# S203X.net
KiCad netlist of a schematic drawn in EAGLE
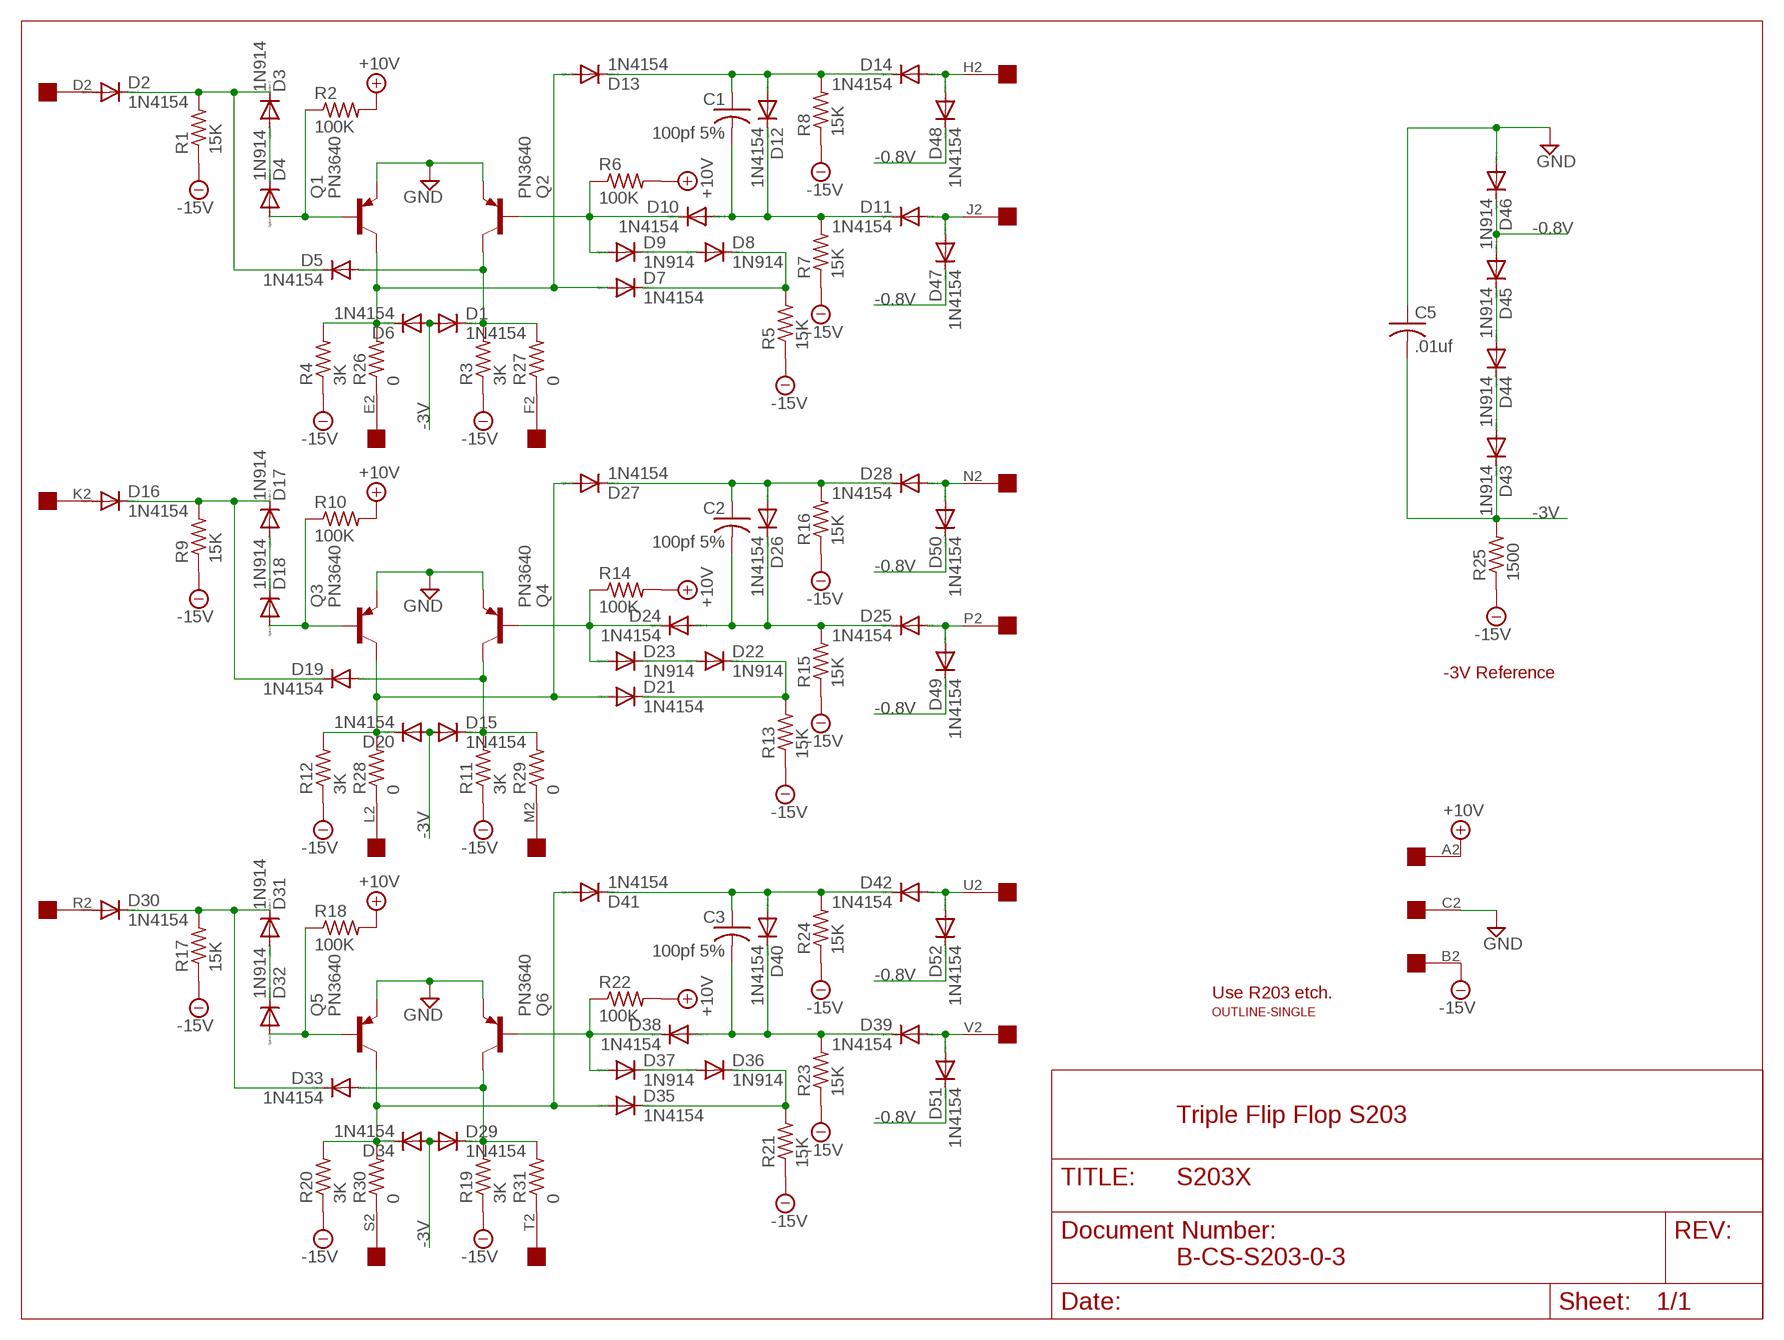
[diagram p0: schematic, sheet 1]

(export (version "E")
  (design (tool "Eeschema 10.0.6"))
  (components
    (comp (ref "C1")
      (value "100pf 5%")
      (footprint "eagle-import:C050-025X075")
      (libsource (lib "eagle-import") (part "C-US050-025X075"))
    )
    (comp (ref "C2")
      (value "100pf 5%")
      (footprint "eagle-import:C050-025X075")
      (libsource (lib "eagle-import") (part "C-US050-025X075"))
    )
    (comp (ref "C3")
      (value "100pf 5%")
      (footprint "eagle-import:C050-025X075")
      (libsource (lib "eagle-import") (part "C-US050-025X075"))
    )
    (comp (ref "C5")
      (value ".01uf")
      (footprint "eagle-import:C050-025X075")
      (libsource (lib "eagle-import") (part "C-US050-025X075"))
    )
    (comp (ref "D1")
      (value "1N4154")
      (footprint "eagle-import:DO35-10")
      (libsource (lib "eagle-import") (part "1N4148DO35-10"))
    )
    (comp (ref "D2")
      (value "1N4154")
      (footprint "eagle-import:DO35-10")
      (libsource (lib "eagle-import") (part "1N4148DO35-10"))
    )
    (comp (ref "D3")
      (value "1N914")
      (footprint "eagle-import:DO35-10")
      (libsource (lib "eagle-import") (part "1N4148DO35-10"))
    )
    (comp (ref "D4")
      (value "1N914")
      (footprint "eagle-import:DO35-10")
      (libsource (lib "eagle-import") (part "1N4148DO35-10"))
    )
    (comp (ref "D5")
      (value "1N4154")
      (footprint "eagle-import:DO35-10")
      (libsource (lib "eagle-import") (part "1N4148DO35-10"))
    )
    (comp (ref "D6")
      (value "1N4154")
      (footprint "eagle-import:DO35-10")
      (libsource (lib "eagle-import") (part "1N4148DO35-10"))
    )
    (comp (ref "D7")
      (value "1N4154")
      (footprint "eagle-import:DO35-10")
      (libsource (lib "eagle-import") (part "1N4148DO35-10"))
    )
    (comp (ref "D8")
      (value "1N914")
      (footprint "eagle-import:DO35-10")
      (libsource (lib "eagle-import") (part "1N4148DO35-10"))
    )
    (comp (ref "D9")
      (value "1N914")
      (footprint "eagle-import:DO35-10")
      (libsource (lib "eagle-import") (part "1N4148DO35-10"))
    )
    (comp (ref "D10")
      (value "1N4154")
      (footprint "eagle-import:DO35-10")
      (libsource (lib "eagle-import") (part "1N4148DO35-10"))
    )
    (comp (ref "D11")
      (value "1N4154")
      (footprint "eagle-import:DO35-10")
      (libsource (lib "eagle-import") (part "1N4148DO35-10"))
    )
    (comp (ref "D12")
      (value "1N4154")
      (footprint "eagle-import:DO35-10")
      (libsource (lib "eagle-import") (part "1N4148DO35-10"))
    )
    (comp (ref "D13")
      (value "1N4154")
      (footprint "eagle-import:DO35-10")
      (libsource (lib "eagle-import") (part "1N4148DO35-10"))
    )
    (comp (ref "D14")
      (value "1N4154")
      (footprint "eagle-import:DO35-10")
      (libsource (lib "eagle-import") (part "1N4148DO35-10"))
    )
    (comp (ref "D15")
      (value "1N4154")
      (footprint "eagle-import:DO35-10")
      (libsource (lib "eagle-import") (part "1N4148DO35-10"))
    )
    (comp (ref "D16")
      (value "1N4154")
      (footprint "eagle-import:DO35-10")
      (libsource (lib "eagle-import") (part "1N4148DO35-10"))
    )
    (comp (ref "D17")
      (value "1N914")
      (footprint "eagle-import:DO35-10")
      (libsource (lib "eagle-import") (part "1N4148DO35-10"))
    )
    (comp (ref "D18")
      (value "1N914")
      (footprint "eagle-import:DO35-10")
      (libsource (lib "eagle-import") (part "1N4148DO35-10"))
    )
    (comp (ref "D19")
      (value "1N4154")
      (footprint "eagle-import:DO35-10")
      (libsource (lib "eagle-import") (part "1N4148DO35-10"))
    )
    (comp (ref "D20")
      (value "1N4154")
      (footprint "eagle-import:DO35-10")
      (libsource (lib "eagle-import") (part "1N4148DO35-10"))
    )
    (comp (ref "D21")
      (value "1N4154")
      (footprint "eagle-import:DO35-10")
      (libsource (lib "eagle-import") (part "1N4148DO35-10"))
    )
    (comp (ref "D22")
      (value "1N914")
      (footprint "eagle-import:DO35-10")
      (libsource (lib "eagle-import") (part "1N4148DO35-10"))
    )
    (comp (ref "D23")
      (value "1N914")
      (footprint "eagle-import:DO35-10")
      (libsource (lib "eagle-import") (part "1N4148DO35-10"))
    )
    (comp (ref "D24")
      (value "1N4154")
      (footprint "eagle-import:DO35-10")
      (libsource (lib "eagle-import") (part "1N4148DO35-10"))
    )
    (comp (ref "D25")
      (value "1N4154")
      (footprint "eagle-import:DO35-10")
      (libsource (lib "eagle-import") (part "1N4148DO35-10"))
    )
    (comp (ref "D26")
      (value "1N4154")
      (footprint "eagle-import:DO35-10")
      (libsource (lib "eagle-import") (part "1N4148DO35-10"))
    )
    (comp (ref "D27")
      (value "1N4154")
      (footprint "eagle-import:DO35-10")
      (libsource (lib "eagle-import") (part "1N4148DO35-10"))
    )
    (comp (ref "D28")
      (value "1N4154")
      (footprint "eagle-import:DO35-10")
      (libsource (lib "eagle-import") (part "1N4148DO35-10"))
    )
    (comp (ref "D29")
      (value "1N4154")
      (footprint "eagle-import:DO35-10")
      (libsource (lib "eagle-import") (part "1N4148DO35-10"))
    )
    (comp (ref "D30")
      (value "1N4154")
      (footprint "eagle-import:DO35-10")
      (libsource (lib "eagle-import") (part "1N4148DO35-10"))
    )
    (comp (ref "D31")
      (value "1N914")
      (footprint "eagle-import:DO35-10")
      (libsource (lib "eagle-import") (part "1N4148DO35-10"))
    )
    (comp (ref "D32")
      (value "1N914")
      (footprint "eagle-import:DO35-10")
      (libsource (lib "eagle-import") (part "1N4148DO35-10"))
    )
    (comp (ref "D33")
      (value "1N4154")
      (footprint "eagle-import:DO35-10")
      (libsource (lib "eagle-import") (part "1N4148DO35-10"))
    )
    (comp (ref "D34")
      (value "1N4154")
      (footprint "eagle-import:DO35-10")
      (libsource (lib "eagle-import") (part "1N4148DO35-10"))
    )
    (comp (ref "D35")
      (value "1N4154")
      (footprint "eagle-import:DO35-10")
      (libsource (lib "eagle-import") (part "1N4148DO35-10"))
    )
    (comp (ref "D36")
      (value "1N914")
      (footprint "eagle-import:DO35-10")
      (libsource (lib "eagle-import") (part "1N4148DO35-10"))
    )
    (comp (ref "D37")
      (value "1N914")
      (footprint "eagle-import:DO35-10")
      (libsource (lib "eagle-import") (part "1N4148DO35-10"))
    )
    (comp (ref "D38")
      (value "1N4154")
      (footprint "eagle-import:DO35-10")
      (libsource (lib "eagle-import") (part "1N4148DO35-10"))
    )
    (comp (ref "D39")
      (value "1N4154")
      (footprint "eagle-import:DO35-10")
      (libsource (lib "eagle-import") (part "1N4148DO35-10"))
    )
    (comp (ref "D40")
      (value "1N4154")
      (footprint "eagle-import:DO35-10")
      (libsource (lib "eagle-import") (part "1N4148DO35-10"))
    )
    (comp (ref "D41")
      (value "1N4154")
      (footprint "eagle-import:DO35-10")
      (libsource (lib "eagle-import") (part "1N4148DO35-10"))
    )
    (comp (ref "D42")
      (value "1N4154")
      (footprint "eagle-import:DO35-10")
      (libsource (lib "eagle-import") (part "1N4148DO35-10"))
    )
    (comp (ref "D43")
      (value "1N914")
      (footprint "eagle-import:DO35-10")
      (libsource (lib "eagle-import") (part "1N4148DO35-10"))
    )
    (comp (ref "D44")
      (value "1N914")
      (footprint "eagle-import:DO35-10")
      (libsource (lib "eagle-import") (part "1N4148DO35-10"))
    )
    (comp (ref "D45")
      (value "1N914")
      (footprint "eagle-import:DO35-10")
      (libsource (lib "eagle-import") (part "1N4148DO35-10"))
    )
    (comp (ref "D46")
      (value "1N914")
      (footprint "eagle-import:DO35-10")
      (libsource (lib "eagle-import") (part "1N4148DO35-10"))
    )
    (comp (ref "D47")
      (value "1N4154")
      (footprint "eagle-import:DO35-10")
      (libsource (lib "eagle-import") (part "1N4148DO35-10"))
    )
    (comp (ref "D48")
      (value "1N4154")
      (footprint "eagle-import:DO35-10")
      (libsource (lib "eagle-import") (part "1N4148DO35-10"))
    )
    (comp (ref "D49")
      (value "1N4154")
      (footprint "eagle-import:DO35-10")
      (libsource (lib "eagle-import") (part "1N4148DO35-10"))
    )
    (comp (ref "D50")
      (value "1N4154")
      (footprint "eagle-import:DO35-10")
      (libsource (lib "eagle-import") (part "1N4148DO35-10"))
    )
    (comp (ref "D51")
      (value "1N4154")
      (footprint "eagle-import:DO35-10")
      (libsource (lib "eagle-import") (part "1N4148DO35-10"))
    )
    (comp (ref "D52")
      (value "1N4154")
      (footprint "eagle-import:DO35-10")
      (libsource (lib "eagle-import") (part "1N4148DO35-10"))
    )
    (comp (ref "Q1")
      (value "PN3640")
      (footprint "eagle-import:TO39")
      (libsource (lib "eagle-import") (part "2N3637"))
    )
    (comp (ref "Q2")
      (value "PN3640")
      (footprint "eagle-import:TO39")
      (libsource (lib "eagle-import") (part "2N3637"))
    )
    (comp (ref "Q3")
      (value "PN3640")
      (footprint "eagle-import:TO39")
      (libsource (lib "eagle-import") (part "2N3637"))
    )
    (comp (ref "Q4")
      (value "PN3640")
      (footprint "eagle-import:TO39")
      (libsource (lib "eagle-import") (part "2N3637"))
    )
    (comp (ref "Q5")
      (value "PN3640")
      (footprint "eagle-import:TO39")
      (libsource (lib "eagle-import") (part "2N3637"))
    )
    (comp (ref "Q6")
      (value "PN3640")
      (footprint "eagle-import:TO39")
      (libsource (lib "eagle-import") (part "2N3637"))
    )
    (comp (ref "R1")
      (value "15K")
      (footprint "eagle-import:0207_10")
      (libsource (lib "eagle-import") (part "R-US_0207/10"))
    )
    (comp (ref "R2")
      (value "100K")
      (footprint "eagle-import:0207_10")
      (libsource (lib "eagle-import") (part "R-US_0207/10"))
    )
    (comp (ref "R3")
      (value "3K")
      (footprint "eagle-import:0207_10")
      (libsource (lib "eagle-import") (part "R-US_0207/10"))
    )
    (comp (ref "R4")
      (value "3K")
      (footprint "eagle-import:0207_10")
      (libsource (lib "eagle-import") (part "R-US_0207/10"))
    )
    (comp (ref "R5")
      (value "15K")
      (footprint "eagle-import:0207_10")
      (libsource (lib "eagle-import") (part "R-US_0207/10"))
    )
    (comp (ref "R6")
      (value "100K")
      (footprint "eagle-import:0207_10")
      (libsource (lib "eagle-import") (part "R-US_0207/10"))
    )
    (comp (ref "R7")
      (value "15K")
      (footprint "eagle-import:0207_10")
      (libsource (lib "eagle-import") (part "R-US_0207/10"))
    )
    (comp (ref "R8")
      (value "15K")
      (footprint "eagle-import:0207_10")
      (libsource (lib "eagle-import") (part "R-US_0207/10"))
    )
    (comp (ref "R9")
      (value "15K")
      (footprint "eagle-import:0207_10")
      (libsource (lib "eagle-import") (part "R-US_0207/10"))
    )
    (comp (ref "R10")
      (value "100K")
      (footprint "eagle-import:0207_10")
      (libsource (lib "eagle-import") (part "R-US_0207/10"))
    )
    (comp (ref "R11")
      (value "3K")
      (footprint "eagle-import:0207_10")
      (libsource (lib "eagle-import") (part "R-US_0207/10"))
    )
    (comp (ref "R12")
      (value "3K")
      (footprint "eagle-import:0207_10")
      (libsource (lib "eagle-import") (part "R-US_0207/10"))
    )
    (comp (ref "R13")
      (value "15K")
      (footprint "eagle-import:0207_10")
      (libsource (lib "eagle-import") (part "R-US_0207/10"))
    )
    (comp (ref "R14")
      (value "100K")
      (footprint "eagle-import:0207_10")
      (libsource (lib "eagle-import") (part "R-US_0207/10"))
    )
    (comp (ref "R15")
      (value "15K")
      (footprint "eagle-import:0207_10")
      (libsource (lib "eagle-import") (part "R-US_0207/10"))
    )
    (comp (ref "R16")
      (value "15K")
      (footprint "eagle-import:0207_10")
      (libsource (lib "eagle-import") (part "R-US_0207/10"))
    )
    (comp (ref "R17")
      (value "15K")
      (footprint "eagle-import:0207_10")
      (libsource (lib "eagle-import") (part "R-US_0207/10"))
    )
    (comp (ref "R18")
      (value "100K")
      (footprint "eagle-import:0207_10")
      (libsource (lib "eagle-import") (part "R-US_0207/10"))
    )
    (comp (ref "R19")
      (value "3K")
      (footprint "eagle-import:0207_10")
      (libsource (lib "eagle-import") (part "R-US_0207/10"))
    )
    (comp (ref "R20")
      (value "3K")
      (footprint "eagle-import:0207_10")
      (libsource (lib "eagle-import") (part "R-US_0207/10"))
    )
    (comp (ref "R21")
      (value "15K")
      (footprint "eagle-import:0207_10")
      (libsource (lib "eagle-import") (part "R-US_0207/10"))
    )
    (comp (ref "R22")
      (value "100K")
      (footprint "eagle-import:0207_10")
      (libsource (lib "eagle-import") (part "R-US_0207/10"))
    )
    (comp (ref "R23")
      (value "15K")
      (footprint "eagle-import:0207_10")
      (libsource (lib "eagle-import") (part "R-US_0207/10"))
    )
    (comp (ref "R24")
      (value "15K")
      (footprint "eagle-import:0207_10")
      (libsource (lib "eagle-import") (part "R-US_0207/10"))
    )
    (comp (ref "R25")
      (value "1500")
      (footprint "eagle-import:0207_10")
      (libsource (lib "eagle-import") (part "R-US_0207/10"))
    )
    (comp (ref "R26")
      (value "0")
      (footprint "eagle-import:0207_10")
      (libsource (lib "eagle-import") (part "R-US_0207/10"))
    )
    (comp (ref "R27")
      (value "0")
      (footprint "eagle-import:0207_10")
      (libsource (lib "eagle-import") (part "R-US_0207/10"))
    )
    (comp (ref "R28")
      (value "0")
      (footprint "eagle-import:0207_10")
      (libsource (lib "eagle-import") (part "R-US_0207/10"))
    )
    (comp (ref "R29")
      (value "0")
      (footprint "eagle-import:0207_10")
      (libsource (lib "eagle-import") (part "R-US_0207/10"))
    )
    (comp (ref "R30")
      (value "0")
      (footprint "eagle-import:0207_10")
      (libsource (lib "eagle-import") (part "R-US_0207/10"))
    )
    (comp (ref "R31")
      (value "0")
      (footprint "eagle-import:0207_10")
      (libsource (lib "eagle-import") (part "R-US_0207/10"))
    )
    (comp (ref "U$1")
      (value "OUTLINE-SINGLE")
      (footprint "eagle-import:SINGLE")
      (libsource (lib "eagle-import") (part "OUTLINE-SINGLE"))
    )
    (comp (ref "U$2")
      (value "EDGE-1")
      (footprint "eagle-import:EDGE-CON1")
      (libsource (lib "eagle-import") (part "EDGE-1"))
    )
  )
  (nets
    (net (code "1") (name "+10V") (class "Default")
      (node (ref "R10") (pin "2") (pinfunction "2_2") (pintype "passive"))
      (node (ref "R14") (pin "2") (pinfunction "2_2") (pintype "passive"))
      (node (ref "R18") (pin "2") (pinfunction "2_2") (pintype "passive"))
      (node (ref "R2") (pin "2") (pinfunction "2_2") (pintype "passive"))
      (node (ref "R22") (pin "2") (pinfunction "2_2") (pintype "passive"))
      (node (ref "R6") (pin "2") (pinfunction "2_2") (pintype "passive"))
      (node (ref "U$2") (pin "A2") (pinfunction "1_A2") (pintype "bidirectional"))
    )
    (net (code "2") (name "-15V") (class "Default")
      (node (ref "R1") (pin "1") (pinfunction "1_1") (pintype "passive"))
      (node (ref "R11") (pin "1") (pinfunction "1_1") (pintype "passive"))
      (node (ref "R12") (pin "1") (pinfunction "1_1") (pintype "passive"))
      (node (ref "R13") (pin "1") (pinfunction "1_1") (pintype "passive"))
      (node (ref "R15") (pin "1") (pinfunction "1_1") (pintype "passive"))
      (node (ref "R16") (pin "1") (pinfunction "1_1") (pintype "passive"))
      (node (ref "R17") (pin "1") (pinfunction "1_1") (pintype "passive"))
      (node (ref "R19") (pin "1") (pinfunction "1_1") (pintype "passive"))
      (node (ref "R20") (pin "1") (pinfunction "1_1") (pintype "passive"))
      (node (ref "R21") (pin "1") (pinfunction "1_1") (pintype "passive"))
      (node (ref "R23") (pin "1") (pinfunction "1_1") (pintype "passive"))
      (node (ref "R24") (pin "1") (pinfunction "1_1") (pintype "passive"))
      (node (ref "R25") (pin "1") (pinfunction "1_1") (pintype "passive"))
      (node (ref "R3") (pin "1") (pinfunction "1_1") (pintype "passive"))
      (node (ref "R4") (pin "1") (pinfunction "1_1") (pintype "passive"))
      (node (ref "R5") (pin "1") (pinfunction "1_1") (pintype "passive"))
      (node (ref "R7") (pin "1") (pinfunction "1_1") (pintype "passive"))
      (node (ref "R8") (pin "1") (pinfunction "1_1") (pintype "passive"))
      (node (ref "R9") (pin "1") (pinfunction "1_1") (pintype "passive"))
      (node (ref "U$2") (pin "B2") (pinfunction "1_B2") (pintype "bidirectional"))
    )
    (net (code "3") (name "/-0.8V") (class "Default")
      (node (ref "D45") (pin "A") (pinfunction "A_A") (pintype "passive"))
      (node (ref "D46") (pin "C") (pinfunction "C_C") (pintype "passive"))
      (node (ref "D47") (pin "C") (pinfunction "C_C") (pintype "passive"))
      (node (ref "D48") (pin "C") (pinfunction "C_C") (pintype "passive"))
      (node (ref "D49") (pin "C") (pinfunction "C_C") (pintype "passive"))
      (node (ref "D50") (pin "C") (pinfunction "C_C") (pintype "passive"))
      (node (ref "D51") (pin "C") (pinfunction "C_C") (pintype "passive"))
      (node (ref "D52") (pin "C") (pinfunction "C_C") (pintype "passive"))
    )
    (net (code "4") (name "/-3V") (class "Default")
      (node (ref "C5") (pin "2") (pinfunction "2_2") (pintype "passive"))
      (node (ref "D1") (pin "A") (pinfunction "A_A") (pintype "passive"))
      (node (ref "D15") (pin "A") (pinfunction "A_A") (pintype "passive"))
      (node (ref "D20") (pin "A") (pinfunction "A_A") (pintype "passive"))
      (node (ref "D29") (pin "A") (pinfunction "A_A") (pintype "passive"))
      (node (ref "D34") (pin "A") (pinfunction "A_A") (pintype "passive"))
      (node (ref "D43") (pin "C") (pinfunction "C_C") (pintype "passive"))
      (node (ref "D6") (pin "A") (pinfunction "A_A") (pintype "passive"))
      (node (ref "R25") (pin "2") (pinfunction "2_2") (pintype "passive"))
    )
    (net (code "5") (name "GND") (class "Default")
      (node (ref "C5") (pin "1") (pinfunction "1_1") (pintype "passive"))
      (node (ref "D46") (pin "A") (pinfunction "A_A") (pintype "passive"))
      (node (ref "Q1") (pin "1") (pinfunction "E_1") (pintype "passive"))
      (node (ref "Q2") (pin "1") (pinfunction "E_1") (pintype "passive"))
      (node (ref "Q3") (pin "1") (pinfunction "E_1") (pintype "passive"))
      (node (ref "Q4") (pin "1") (pinfunction "E_1") (pintype "passive"))
      (node (ref "Q5") (pin "1") (pinfunction "E_1") (pintype "passive"))
      (node (ref "Q6") (pin "1") (pinfunction "E_1") (pintype "passive"))
      (node (ref "U$2") (pin "C2") (pinfunction "1_C2") (pintype "bidirectional"))
    )
    (net (code "6") (name "Net-(C1-Pad1)") (class "Default")
      (node (ref "C1") (pin "1") (pinfunction "1_1") (pintype "passive"))
      (node (ref "D12") (pin "A") (pinfunction "A_A") (pintype "passive"))
      (node (ref "D13") (pin "C") (pinfunction "C_C") (pintype "passive"))
      (node (ref "D14") (pin "C") (pinfunction "C_C") (pintype "passive"))
      (node (ref "R8") (pin "2") (pinfunction "2_2") (pintype "passive"))
    )
    (net (code "7") (name "Net-(C1-Pad2)") (class "Default")
      (node (ref "C1") (pin "2") (pinfunction "2_2") (pintype "passive"))
      (node (ref "D10") (pin "A") (pinfunction "A_A") (pintype "passive"))
      (node (ref "D11") (pin "C") (pinfunction "C_C") (pintype "passive"))
      (node (ref "D12") (pin "C") (pinfunction "C_C") (pintype "passive"))
      (node (ref "R7") (pin "2") (pinfunction "2_2") (pintype "passive"))
    )
    (net (code "8") (name "Net-(C2-Pad1)") (class "Default")
      (node (ref "C2") (pin "1") (pinfunction "1_1") (pintype "passive"))
      (node (ref "D26") (pin "A") (pinfunction "A_A") (pintype "passive"))
      (node (ref "D27") (pin "C") (pinfunction "C_C") (pintype "passive"))
      (node (ref "D28") (pin "C") (pinfunction "C_C") (pintype "passive"))
      (node (ref "R16") (pin "2") (pinfunction "2_2") (pintype "passive"))
    )
    (net (code "9") (name "Net-(C2-Pad2)") (class "Default")
      (node (ref "C2") (pin "2") (pinfunction "2_2") (pintype "passive"))
      (node (ref "D24") (pin "A") (pinfunction "A_A") (pintype "passive"))
      (node (ref "D25") (pin "C") (pinfunction "C_C") (pintype "passive"))
      (node (ref "D26") (pin "C") (pinfunction "C_C") (pintype "passive"))
      (node (ref "R15") (pin "2") (pinfunction "2_2") (pintype "passive"))
    )
    (net (code "10") (name "Net-(C3-Pad1)") (class "Default")
      (node (ref "C3") (pin "1") (pinfunction "1_1") (pintype "passive"))
      (node (ref "D40") (pin "A") (pinfunction "A_A") (pintype "passive"))
      (node (ref "D41") (pin "C") (pinfunction "C_C") (pintype "passive"))
      (node (ref "D42") (pin "C") (pinfunction "C_C") (pintype "passive"))
      (node (ref "R24") (pin "2") (pinfunction "2_2") (pintype "passive"))
    )
    (net (code "11") (name "Net-(C3-Pad2)") (class "Default")
      (node (ref "C3") (pin "2") (pinfunction "2_2") (pintype "passive"))
      (node (ref "D38") (pin "A") (pinfunction "A_A") (pintype "passive"))
      (node (ref "D39") (pin "C") (pinfunction "C_C") (pintype "passive"))
      (node (ref "D40") (pin "C") (pinfunction "C_C") (pintype "passive"))
      (node (ref "R23") (pin "2") (pinfunction "2_2") (pintype "passive"))
    )
    (net (code "12") (name "Net-(D2-PadC)") (class "Default")
      (node (ref "D2") (pin "C") (pinfunction "C_C") (pintype "passive"))
      (node (ref "D3") (pin "C") (pinfunction "C_C") (pintype "passive"))
      (node (ref "D5") (pin "C") (pinfunction "C_C") (pintype "passive"))
      (node (ref "R1") (pin "2") (pinfunction "2_2") (pintype "passive"))
    )
    (net (code "13") (name "Net-(D3-PadA)") (class "Default")
      (node (ref "D3") (pin "A") (pinfunction "A_A") (pintype "passive"))
      (node (ref "D4") (pin "C") (pinfunction "C_C") (pintype "passive"))
    )
    (net (code "14") (name "Net-(D7-PadC)") (class "Default")
      (node (ref "D7") (pin "C") (pinfunction "C_C") (pintype "passive"))
      (node (ref "D8") (pin "C") (pinfunction "C_C") (pintype "passive"))
      (node (ref "R5") (pin "2") (pinfunction "2_2") (pintype "passive"))
    )
    (net (code "15") (name "Net-(D8-PadA)") (class "Default")
      (node (ref "D8") (pin "A") (pinfunction "A_A") (pintype "passive"))
      (node (ref "D9") (pin "C") (pinfunction "C_C") (pintype "passive"))
    )
    (net (code "16") (name "Net-(D16-PadC)") (class "Default")
      (node (ref "D16") (pin "C") (pinfunction "C_C") (pintype "passive"))
      (node (ref "D17") (pin "C") (pinfunction "C_C") (pintype "passive"))
      (node (ref "D19") (pin "C") (pinfunction "C_C") (pintype "passive"))
      (node (ref "R9") (pin "2") (pinfunction "2_2") (pintype "passive"))
    )
    (net (code "17") (name "Net-(D17-PadA)") (class "Default")
      (node (ref "D17") (pin "A") (pinfunction "A_A") (pintype "passive"))
      (node (ref "D18") (pin "C") (pinfunction "C_C") (pintype "passive"))
    )
    (net (code "18") (name "Net-(D21-PadC)") (class "Default")
      (node (ref "D21") (pin "C") (pinfunction "C_C") (pintype "passive"))
      (node (ref "D22") (pin "C") (pinfunction "C_C") (pintype "passive"))
      (node (ref "R13") (pin "2") (pinfunction "2_2") (pintype "passive"))
    )
    (net (code "19") (name "Net-(D22-PadA)") (class "Default")
      (node (ref "D22") (pin "A") (pinfunction "A_A") (pintype "passive"))
      (node (ref "D23") (pin "C") (pinfunction "C_C") (pintype "passive"))
    )
    (net (code "20") (name "Net-(D30-PadC)") (class "Default")
      (node (ref "D30") (pin "C") (pinfunction "C_C") (pintype "passive"))
      (node (ref "D31") (pin "C") (pinfunction "C_C") (pintype "passive"))
      (node (ref "D33") (pin "C") (pinfunction "C_C") (pintype "passive"))
      (node (ref "R17") (pin "2") (pinfunction "2_2") (pintype "passive"))
    )
    (net (code "21") (name "Net-(D31-PadA)") (class "Default")
      (node (ref "D31") (pin "A") (pinfunction "A_A") (pintype "passive"))
      (node (ref "D32") (pin "C") (pinfunction "C_C") (pintype "passive"))
    )
    (net (code "22") (name "Net-(D35-PadC)") (class "Default")
      (node (ref "D35") (pin "C") (pinfunction "C_C") (pintype "passive"))
      (node (ref "D36") (pin "C") (pinfunction "C_C") (pintype "passive"))
      (node (ref "R21") (pin "2") (pinfunction "2_2") (pintype "passive"))
    )
    (net (code "23") (name "Net-(D36-PadA)") (class "Default")
      (node (ref "D36") (pin "A") (pinfunction "A_A") (pintype "passive"))
      (node (ref "D37") (pin "C") (pinfunction "C_C") (pintype "passive"))
    )
    (net (code "24") (name "Net-(D43-PadA)") (class "Default")
      (node (ref "D43") (pin "A") (pinfunction "A_A") (pintype "passive"))
      (node (ref "D44") (pin "C") (pinfunction "C_C") (pintype "passive"))
    )
    (net (code "25") (name "Net-(D44-PadA)") (class "Default")
      (node (ref "D44") (pin "A") (pinfunction "A_A") (pintype "passive"))
      (node (ref "D45") (pin "C") (pinfunction "C_C") (pintype "passive"))
    )
    (net (code "26") (name "Net-(Q1-B)") (class "Default")
      (node (ref "D4") (pin "A") (pinfunction "A_A") (pintype "passive"))
      (node (ref "Q1") (pin "2") (pinfunction "B_2") (pintype "passive"))
      (node (ref "R2") (pin "1") (pinfunction "1_1") (pintype "passive"))
    )
    (net (code "27") (name "Net-(Q1-C)") (class "Default")
      (node (ref "D13") (pin "A") (pinfunction "A_A") (pintype "passive"))
      (node (ref "D6") (pin "C") (pinfunction "C_C") (pintype "passive"))
      (node (ref "D7") (pin "A") (pinfunction "A_A") (pintype "passive"))
      (node (ref "Q1") (pin "3") (pinfunction "C_3") (pintype "passive"))
      (node (ref "R26") (pin "2") (pinfunction "2_2") (pintype "passive"))
      (node (ref "R4") (pin "2") (pinfunction "2_2") (pintype "passive"))
    )
    (net (code "28") (name "Net-(Q2-B)") (class "Default")
      (node (ref "D10") (pin "C") (pinfunction "C_C") (pintype "passive"))
      (node (ref "D9") (pin "A") (pinfunction "A_A") (pintype "passive"))
      (node (ref "Q2") (pin "2") (pinfunction "B_2") (pintype "passive"))
      (node (ref "R6") (pin "1") (pinfunction "1_1") (pintype "passive"))
    )
    (net (code "29") (name "Net-(Q2-C)") (class "Default")
      (node (ref "D1") (pin "C") (pinfunction "C_C") (pintype "passive"))
      (node (ref "D5") (pin "A") (pinfunction "A_A") (pintype "passive"))
      (node (ref "Q2") (pin "3") (pinfunction "C_3") (pintype "passive"))
      (node (ref "R27") (pin "2") (pinfunction "2_2") (pintype "passive"))
      (node (ref "R3") (pin "2") (pinfunction "2_2") (pintype "passive"))
    )
    (net (code "30") (name "Net-(Q3-B)") (class "Default")
      (node (ref "D18") (pin "A") (pinfunction "A_A") (pintype "passive"))
      (node (ref "Q3") (pin "2") (pinfunction "B_2") (pintype "passive"))
      (node (ref "R10") (pin "1") (pinfunction "1_1") (pintype "passive"))
    )
    (net (code "31") (name "Net-(Q3-C)") (class "Default")
      (node (ref "D20") (pin "C") (pinfunction "C_C") (pintype "passive"))
      (node (ref "D21") (pin "A") (pinfunction "A_A") (pintype "passive"))
      (node (ref "D27") (pin "A") (pinfunction "A_A") (pintype "passive"))
      (node (ref "Q3") (pin "3") (pinfunction "C_3") (pintype "passive"))
      (node (ref "R12") (pin "2") (pinfunction "2_2") (pintype "passive"))
      (node (ref "R28") (pin "2") (pinfunction "2_2") (pintype "passive"))
    )
    (net (code "32") (name "Net-(Q4-B)") (class "Default")
      (node (ref "D23") (pin "A") (pinfunction "A_A") (pintype "passive"))
      (node (ref "D24") (pin "C") (pinfunction "C_C") (pintype "passive"))
      (node (ref "Q4") (pin "2") (pinfunction "B_2") (pintype "passive"))
      (node (ref "R14") (pin "1") (pinfunction "1_1") (pintype "passive"))
    )
    (net (code "33") (name "Net-(Q4-C)") (class "Default")
      (node (ref "D15") (pin "C") (pinfunction "C_C") (pintype "passive"))
      (node (ref "D19") (pin "A") (pinfunction "A_A") (pintype "passive"))
      (node (ref "Q4") (pin "3") (pinfunction "C_3") (pintype "passive"))
      (node (ref "R11") (pin "2") (pinfunction "2_2") (pintype "passive"))
      (node (ref "R29") (pin "2") (pinfunction "2_2") (pintype "passive"))
    )
    (net (code "34") (name "Net-(Q5-B)") (class "Default")
      (node (ref "D32") (pin "A") (pinfunction "A_A") (pintype "passive"))
      (node (ref "Q5") (pin "2") (pinfunction "B_2") (pintype "passive"))
      (node (ref "R18") (pin "1") (pinfunction "1_1") (pintype "passive"))
    )
    (net (code "35") (name "Net-(Q5-C)") (class "Default")
      (node (ref "D34") (pin "C") (pinfunction "C_C") (pintype "passive"))
      (node (ref "D35") (pin "A") (pinfunction "A_A") (pintype "passive"))
      (node (ref "D41") (pin "A") (pinfunction "A_A") (pintype "passive"))
      (node (ref "Q5") (pin "3") (pinfunction "C_3") (pintype "passive"))
      (node (ref "R20") (pin "2") (pinfunction "2_2") (pintype "passive"))
      (node (ref "R30") (pin "2") (pinfunction "2_2") (pintype "passive"))
    )
    (net (code "36") (name "Net-(Q6-B)") (class "Default")
      (node (ref "D37") (pin "A") (pinfunction "A_A") (pintype "passive"))
      (node (ref "D38") (pin "C") (pinfunction "C_C") (pintype "passive"))
      (node (ref "Q6") (pin "2") (pinfunction "B_2") (pintype "passive"))
      (node (ref "R22") (pin "1") (pinfunction "1_1") (pintype "passive"))
    )
    (net (code "37") (name "Net-(Q6-C)") (class "Default")
      (node (ref "D29") (pin "C") (pinfunction "C_C") (pintype "passive"))
      (node (ref "D33") (pin "A") (pinfunction "A_A") (pintype "passive"))
      (node (ref "Q6") (pin "3") (pinfunction "C_3") (pintype "passive"))
      (node (ref "R19") (pin "2") (pinfunction "2_2") (pintype "passive"))
      (node (ref "R31") (pin "2") (pinfunction "2_2") (pintype "passive"))
    )
    (net (code "38") (name "Net-(U$2D-1)") (class "Default")
      (node (ref "D2") (pin "A") (pinfunction "A_A") (pintype "passive"))
      (node (ref "U$2") (pin "D2") (pinfunction "1_D2") (pintype "bidirectional"))
    )
    (net (code "39") (name "Net-(U$2E-1)") (class "Default")
      (node (ref "R26") (pin "1") (pinfunction "1_1") (pintype "passive"))
      (node (ref "U$2") (pin "E2") (pinfunction "1_E2") (pintype "bidirectional"))
    )
    (net (code "40") (name "Net-(U$2F-1)") (class "Default")
      (node (ref "R27") (pin "1") (pinfunction "1_1") (pintype "passive"))
      (node (ref "U$2") (pin "F2") (pinfunction "1_F2") (pintype "bidirectional"))
    )
    (net (code "41") (name "Net-(U$2G-1)") (class "Default")
      (node (ref "D14") (pin "A") (pinfunction "A_A") (pintype "passive"))
      (node (ref "D48") (pin "A") (pinfunction "A_A") (pintype "passive"))
      (node (ref "U$2") (pin "H2") (pinfunction "1_H2") (pintype "bidirectional"))
    )
    (net (code "42") (name "Net-(U$2H-1)") (class "Default")
      (node (ref "D11") (pin "A") (pinfunction "A_A") (pintype "passive"))
      (node (ref "D47") (pin "A") (pinfunction "A_A") (pintype "passive"))
      (node (ref "U$2") (pin "J2") (pinfunction "1_J2") (pintype "bidirectional"))
    )
    (net (code "43") (name "Net-(U$2I-1)") (class "Default")
      (node (ref "D16") (pin "A") (pinfunction "A_A") (pintype "passive"))
      (node (ref "U$2") (pin "K2") (pinfunction "1_K2") (pintype "bidirectional"))
    )
    (net (code "44") (name "Net-(U$2J-1)") (class "Default")
      (node (ref "R28") (pin "1") (pinfunction "1_1") (pintype "passive"))
      (node (ref "U$2") (pin "L2") (pinfunction "1_L2") (pintype "bidirectional"))
    )
    (net (code "45") (name "Net-(U$2K-1)") (class "Default")
      (node (ref "R29") (pin "1") (pinfunction "1_1") (pintype "passive"))
      (node (ref "U$2") (pin "M2") (pinfunction "1_M2") (pintype "bidirectional"))
    )
    (net (code "46") (name "Net-(U$2L-1)") (class "Default")
      (node (ref "D28") (pin "A") (pinfunction "A_A") (pintype "passive"))
      (node (ref "D50") (pin "A") (pinfunction "A_A") (pintype "passive"))
      (node (ref "U$2") (pin "N2") (pinfunction "1_N2") (pintype "bidirectional"))
    )
    (net (code "47") (name "Net-(U$2M-1)") (class "Default")
      (node (ref "D25") (pin "A") (pinfunction "A_A") (pintype "passive"))
      (node (ref "D49") (pin "A") (pinfunction "A_A") (pintype "passive"))
      (node (ref "U$2") (pin "P2") (pinfunction "1_P2") (pintype "bidirectional"))
    )
    (net (code "48") (name "Net-(U$2N-1)") (class "Default")
      (node (ref "D30") (pin "A") (pinfunction "A_A") (pintype "passive"))
      (node (ref "U$2") (pin "R2") (pinfunction "1_R2") (pintype "bidirectional"))
    )
    (net (code "49") (name "Net-(U$2O-1)") (class "Default")
      (node (ref "R30") (pin "1") (pinfunction "1_1") (pintype "passive"))
      (node (ref "U$2") (pin "S2") (pinfunction "1_S2") (pintype "bidirectional"))
    )
    (net (code "50") (name "Net-(U$2P-1)") (class "Default")
      (node (ref "R31") (pin "1") (pinfunction "1_1") (pintype "passive"))
      (node (ref "U$2") (pin "T2") (pinfunction "1_T2") (pintype "bidirectional"))
    )
    (net (code "51") (name "Net-(U$2Q-1)") (class "Default")
      (node (ref "D42") (pin "A") (pinfunction "A_A") (pintype "passive"))
      (node (ref "D52") (pin "A") (pinfunction "A_A") (pintype "passive"))
      (node (ref "U$2") (pin "U2") (pinfunction "1_U2") (pintype "bidirectional"))
    )
    (net (code "52") (name "Net-(U$2R-1)") (class "Default")
      (node (ref "D39") (pin "A") (pinfunction "A_A") (pintype "passive"))
      (node (ref "D51") (pin "A") (pinfunction "A_A") (pintype "passive"))
      (node (ref "U$2") (pin "V2") (pinfunction "1_V2") (pintype "bidirectional"))
    )
  )
)
